# TOFSensor.net
KiCad netlist of a schematic drawn in Altium Designer
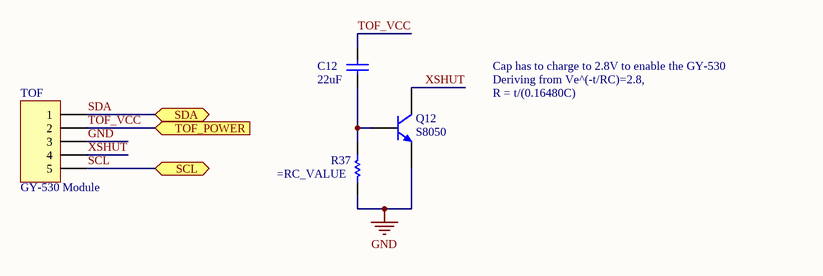
[diagram p0: TOFSensor.SchDoc]

(export (version "E")
  (design (tool "Eeschema 10.0.6"))
  (components
    (comp (ref "C12")
      (value "22uF")
      (footprint "J1-0603")
      (description "Capacitor")
      (fields (field (name "Comment") "Cap") (field (name "PUBLISHER") "Altium Limited"))
      (libsource (lib "Miscellaneous Devices") (part "Cap"))
    )
    (comp (ref "Q12")
      (value "S8050")
      (footprint "SOT23-3M")
      (description "NPN General Purpose Amplifier")
      (fields (field (name "PUBLISHER") "Altium Limited"))
      (libsource (lib "sumo") (part "S8050"))
    )
    (comp (ref "R37")
      (value "Res1")
      (footprint "J1-0603")
      (description "Resistor")
      (fields (field (name "PUBLISHER") "Altium Limited"))
      (libsource (lib "Miscellaneous Devices") (part "Res1"))
    )
    (comp (ref "TOF")
      (value "GY-530 Module")
      (footprint "HDR1X5")
      (description "Header, 5-Pin")
      (fields (field (name "PUBLISHER") "Altium Limited"))
      (libsource (lib "Miscellaneous Connectors") (part "Header 5"))
    )
  )
  (nets
    (net (code "1") (name "/SCL") (class "Default")
      (node (ref "TOF") (pin "5") (pinfunction "5_5") (pintype "passive"))
    )
    (net (code "2") (name "/SDA") (class "Default")
      (node (ref "TOF") (pin "1") (pinfunction "1_1") (pintype "passive"))
    )
    (net (code "3") (name "/TOF_VCC") (class "Default")
      (node (ref "C12") (pin "1") (pinfunction "1_1") (pintype "passive"))
      (node (ref "TOF") (pin "2") (pinfunction "2_2") (pintype "passive"))
    )
    (net (code "4") (name "/XSHUT") (class "Default")
      (node (ref "Q12") (pin "3") (pinfunction "C_3") (pintype "passive"))
      (node (ref "TOF") (pin "4") (pinfunction "4_4") (pintype "passive"))
    )
    (net (code "5") (name "GND") (class "Default")
      (node (ref "Q12") (pin "2") (pinfunction "E_2") (pintype "passive"))
      (node (ref "R37") (pin "1") (pinfunction "1_1") (pintype "passive"))
      (node (ref "TOF") (pin "3") (pinfunction "3_3") (pintype "passive"))
    )
    (net (code "6") (name "Net-(Q12-B)") (class "Default")
      (node (ref "C12") (pin "2") (pinfunction "2_2") (pintype "passive"))
      (node (ref "Q12") (pin "1") (pinfunction "B_1") (pintype "passive"))
      (node (ref "R37") (pin "2") (pinfunction "2_2") (pintype "passive"))
    )
  )
)
